# yard-ice-power.net
KiCad netlist of a schematic drawn in Altium Designer
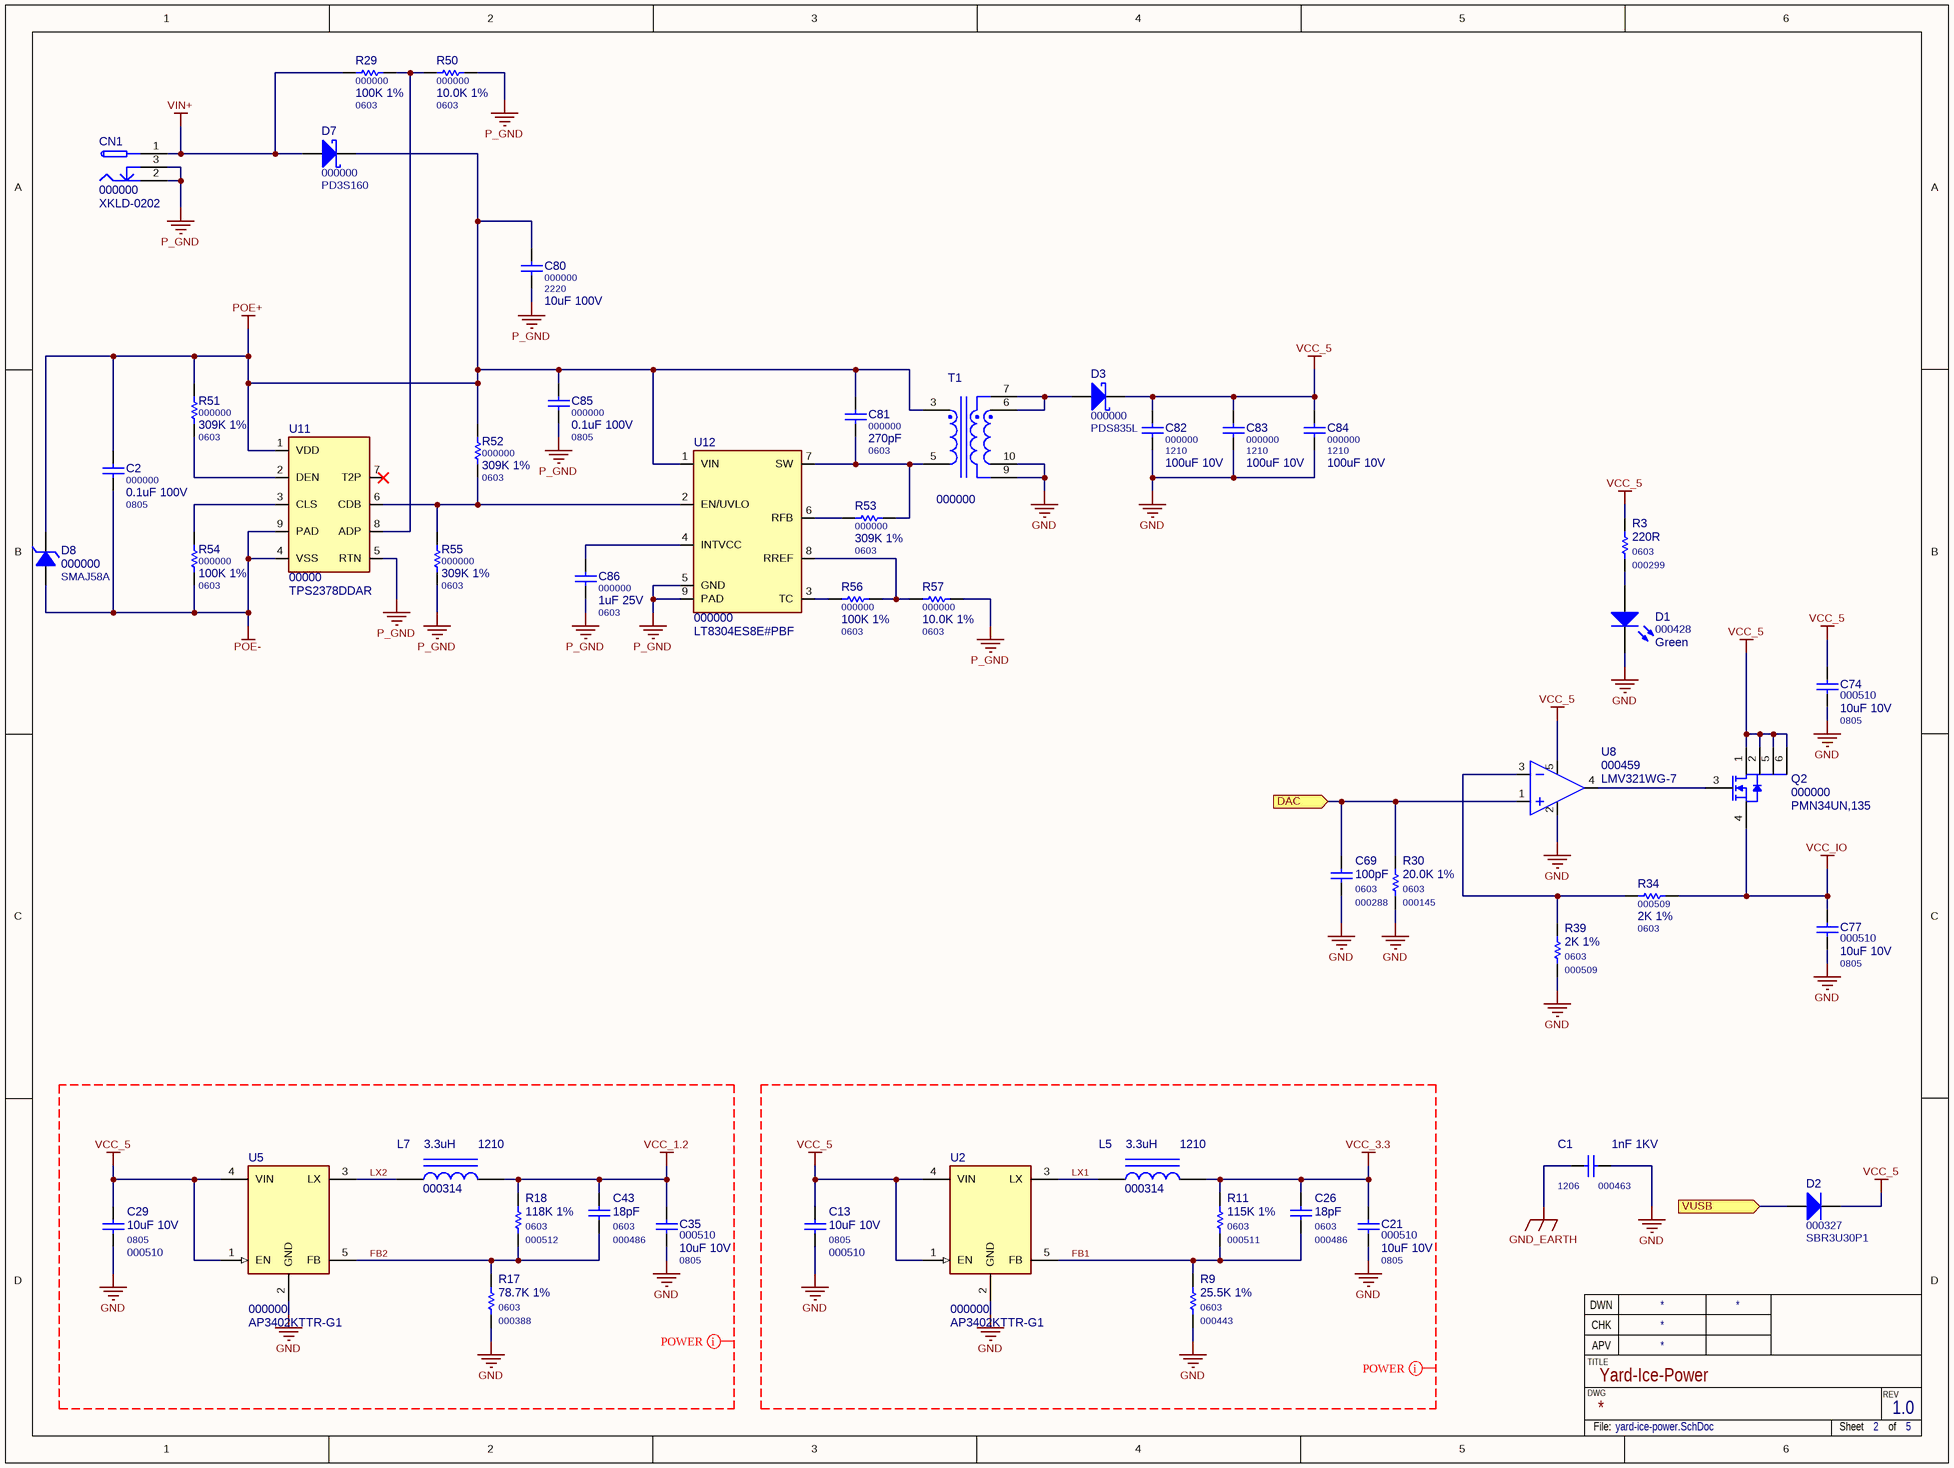
[diagram p0: yard-ice-power.SchDoc]

(export (version "E")
  (design (tool "Eeschema 10.0.6"))
  (components
    (comp (ref "C1")
      (value "000463")
      (footprint "C1206M")
      (description "SMD Ceramic Chip Capacitor - 1206")
      (fields (field (name "ALTIUM_VALUE") "1nF 1KV") (field (name "PACKAGE") "1206"))
      (libsource (lib "discrete-sm") (part "C1206"))
    )
    (comp (ref "C2")
      (value "000000")
      (footprint "C0805HV")
      (description "SMD Ceramic Chip Capacitor - 0805")
      (fields (field (name "ALTIUM_VALUE") "0.1uF 100V") (field (name "PACKAGE") "0805"))
      (libsource (lib "discrete-sm") (part "C0805"))
    )
    (comp (ref "C13")
      (value "000510")
      (footprint "C0805M")
      (description "SMD Ceramic Chip Capacitor - 0805 - X7R")
      (fields
        (field (name "ALTIUM_VALUE") "10uF 10V")
        (field (name "PACKAGE") "0805")
        (field (name "MF") "TDK")
      )
      (libsource (lib "sm_cap") (part "C0805"))
    )
    (comp (ref "C21")
      (value "000510")
      (footprint "C0805M")
      (description "SMD Ceramic Chip Capacitor - 0805 - X7R")
      (fields
        (field (name "ALTIUM_VALUE") "10uF 10V")
        (field (name "PACKAGE") "0805")
        (field (name "MF") "TDK")
      )
      (libsource (lib "sm_cap") (part "C0805"))
    )
    (comp (ref "C26")
      (value "000486")
      (footprint "C0603M")
      (description "SMD Ceramic Chip Capacitor - 0603")
      (fields (field (name "ALTIUM_VALUE") "18pF") (field (name "PACKAGE") "0603"))
      (libsource (lib "discrete-sm") (part "C0603"))
    )
    (comp (ref "C29")
      (value "000510")
      (footprint "C0805M")
      (description "SMD Ceramic Chip Capacitor - 0805 - X7R")
      (fields
        (field (name "ALTIUM_VALUE") "10uF 10V")
        (field (name "PACKAGE") "0805")
        (field (name "MF") "TDK")
      )
      (libsource (lib "sm_cap") (part "C0805"))
    )
    (comp (ref "C35")
      (value "000510")
      (footprint "C0805M")
      (description "SMD Ceramic Chip Capacitor - 0805 - X7R")
      (fields
        (field (name "ALTIUM_VALUE") "10uF 10V")
        (field (name "PACKAGE") "0805")
        (field (name "MF") "TDK")
      )
      (libsource (lib "sm_cap") (part "C0805"))
    )
    (comp (ref "C43")
      (value "000486")
      (footprint "C0603M")
      (description "SMD Ceramic Chip Capacitor - 0603")
      (fields (field (name "ALTIUM_VALUE") "18pF") (field (name "PACKAGE") "0603"))
      (libsource (lib "discrete-sm") (part "C0603"))
    )
    (comp (ref "C69")
      (value "000288")
      (footprint "C0603M")
      (description "SMD Ceramic Chip Capacitor - 0603")
      (fields (field (name "ALTIUM_VALUE") "100pF") (field (name "PACKAGE") "0603"))
      (libsource (lib "discrete-sm") (part "C0603"))
    )
    (comp (ref "C74")
      (value "TDK")
      (footprint "C0805M")
      (description "SMD Ceramic Chip Capacitor - 0805 - X7R")
      (fields (field (name "ALTIUM_VALUE") "10uF 10V") (field (name "PACKAGE") "0805"))
      (libsource (lib "sm_cap") (part "C0805"))
    )
    (comp (ref "C77")
      (value "TDK")
      (footprint "C0805M")
      (description "SMD Ceramic Chip Capacitor - 0805 - X7R")
      (fields (field (name "ALTIUM_VALUE") "10uF 10V") (field (name "PACKAGE") "0805"))
      (libsource (lib "sm_cap") (part "C0805"))
    )
    (comp (ref "C80")
      (value "000000")
      (footprint "C2220M")
      (description "SMD Ceramic Chip Capacitor - 2220")
      (fields
        (field (name "MF") "AVX")
        (field (name "PACKAGE") "2220")
        (field (name "ALTIUM_VALUE") "10uF 100V")
      )
      (libsource (lib "discrete-sm") (part "C2220"))
    )
    (comp (ref "C81")
      (value "000000")
      (footprint "C0603HV")
      (description "SMD Ceramic Chip Capacitor - 0603")
      (fields (field (name "ALTIUM_VALUE") "270pF") (field (name "PACKAGE") "0603"))
      (libsource (lib "discrete-sm") (part "C0603"))
    )
    (comp (ref "C82")
      (value "000000")
      (footprint "C1210M")
      (description "SMD Ceramic Chip Capacitor - 1210")
      (fields
        (field (name "PACKAGE") "1210")
        (field (name "ALTIUM_VALUE") "100uF 10V")
        (field (name "MF") "Taiyo Yuden")
      )
      (libsource (lib "discrete-sm") (part "C1210"))
    )
    (comp (ref "C83")
      (value "000000")
      (footprint "C1210M")
      (description "SMD Ceramic Chip Capacitor - 1210")
      (fields
        (field (name "PACKAGE") "1210")
        (field (name "ALTIUM_VALUE") "100uF 10V")
        (field (name "MF") "Taiyo Yuden")
      )
      (libsource (lib "discrete-sm") (part "C1210"))
    )
    (comp (ref "C84")
      (value "000000")
      (footprint "C1210M")
      (description "SMD Ceramic Chip Capacitor - 1210")
      (fields
        (field (name "PACKAGE") "1210")
        (field (name "ALTIUM_VALUE") "100uF 10V")
        (field (name "MF") "Taiyo Yuden")
      )
      (libsource (lib "discrete-sm") (part "C1210"))
    )
    (comp (ref "C85")
      (value "000000")
      (footprint "C0805HV")
      (description "SMD Ceramic Chip Capacitor - 0805")
      (fields (field (name "ALTIUM_VALUE") "0.1uF 100V") (field (name "PACKAGE") "0805"))
      (libsource (lib "discrete-sm") (part "C0805"))
    )
    (comp (ref "C86")
      (value "000000")
      (footprint "C0603M")
      (description "SMD Ceramic Chip Capacitor - 0603")
      (fields (field (name "ALTIUM_VALUE") "1uF 25V") (field (name "PACKAGE") "0603"))
      (libsource (lib "discrete-sm") (part "C0603"))
    )
    (comp (ref "CN1")
      (value "000000")
      (footprint "KLDX-0202")
      (description "Low Voltage Power Supply Connector")
      (fields (field (name "MF") "KYCON") (field (name "ALTIUM_VALUE") "XKLD-0202"))
      (libsource (lib "kycon") (part "XKLD-0202"))
    )
    (comp (ref "D1")
      (value "000428")
      (footprint "LED0805L LP")
      (description "LED SMD 0805")
      (fields (field (name "ALTIUM_VALUE") "Green"))
      (libsource (lib "discrete-sm") (part "LED0805LP"))
    )
    (comp (ref "D2")
      (value "000327")
      (footprint "PowerDI 123")
      (description "Super Barrier Rectifier")
      (fields (field (name "ALTIUM_VALUE") "SBR3U30P1") (field (name "MF") "Diodes Inc"))
      (libsource (lib "diodes-inc") (part "SBR3U30P1"))
    )
    (comp (ref "D3")
      (value "000000")
      (footprint "PowerDI 5")
      (description "Shottky Barrier Rectifier 25V 8A")
      (fields (field (name "ALTIUM_VALUE") "PDS835L") (field (name "MF") "Diodes Inc"))
      (libsource (lib "diodes-inc") (part "PDS835L"))
    )
    (comp (ref "D7")
      (value "000000")
      (footprint "PowerDI 123")
      (description "Sshottky Barrier Rectifier 60V 1A")
      (fields (field (name "ALTIUM_VALUE") "PD3S160") (field (name "MF") "Diodes Inc"))
      (libsource (lib "diodes-inc") (part "PD3S160"))
    )
    (comp (ref "D8")
      (value "000000")
      (footprint "DO-214AC")
      (description "Unidirectional Transiet Voltage Suppressor")
      (fields (field (name "ALTIUM_VALUE") "SMAJ58A") (field (name "MF") "Bourns"))
      (libsource (lib "bourns") (part "SMAJXXA"))
    )
    (comp (ref "L5")
      (value "000314")
      (footprint "L1210M")
      (description "SMD Wire Wound Inductor -  1210 (3225 metric)")
      (fields
        (field (name "MF") "Murata")
        (field (name "PACKAGE") "1210")
        (field (name "ALTIUM_VALUE") "3.3uH")
      )
      (libsource (lib "discrete-sm") (part "L1210"))
    )
    (comp (ref "L7")
      (value "000314")
      (footprint "L1210M")
      (description "SMD Wire Wound Inductor -  1210 (3225 metric)")
      (fields
        (field (name "MF") "Murata")
        (field (name "PACKAGE") "1210")
        (field (name "ALTIUM_VALUE") "3.3uH")
      )
      (libsource (lib "discrete-sm") (part "L1210"))
    )
    (comp (ref "Q2")
      (value "000000")
      (footprint "SOT-26")
      (description "N-Channel MOSFET 30V 4.9A 6TSOP")
      (fields (field (name "ALTIUM_VALUE") "PMN34UN,135"))
      (libsource (lib "nxp") (part "PMN34UN,135"))
    )
    (comp (ref "R3")
      (value "000299")
      (footprint "R0603M")
      (description "SMD Chip Resistor - 0603")
      (fields (field (name "ALTIUM_VALUE") "220R") (field (name "PACKAGE") "0603"))
      (libsource (lib "discrete-sm") (part "R0603"))
    )
    (comp (ref "R9")
      (value "000443")
      (footprint "R0603M")
      (description "SMD Chip Resistor - 0603")
      (fields (field (name "ALTIUM_VALUE") "25.5K 1%") (field (name "PACKAGE") "0603"))
      (libsource (lib "discrete-sm") (part "R0603"))
    )
    (comp (ref "R11")
      (value "000511")
      (footprint "R0603M")
      (description "SMD Chip Resistor - 0603")
      (fields (field (name "ALTIUM_VALUE") "115K 1%") (field (name "PACKAGE") "0603"))
      (libsource (lib "discrete-sm") (part "R0603"))
    )
    (comp (ref "R17")
      (value "000388")
      (footprint "R0603M")
      (description "SMD Chip Resistor - 0603")
      (fields (field (name "ALTIUM_VALUE") "78.7K 1%") (field (name "PACKAGE") "0603"))
      (libsource (lib "discrete-sm") (part "R0603"))
    )
    (comp (ref "R18")
      (value "000512")
      (footprint "R0603M")
      (description "SMD Chip Resistor - 0603")
      (fields (field (name "ALTIUM_VALUE") "118K 1%") (field (name "PACKAGE") "0603"))
      (libsource (lib "discrete-sm") (part "R0603"))
    )
    (comp (ref "R29")
      (value "000000")
      (footprint "R0603M")
      (description "SMD Chip Resistor - 0603")
      (fields (field (name "ALTIUM_VALUE") "100K 1%") (field (name "PACKAGE") "0603"))
      (libsource (lib "discrete-sm") (part "R0603"))
    )
    (comp (ref "R30")
      (value "000145")
      (footprint "R0603M")
      (description "SMD Chip Resistor - 0603")
      (fields (field (name "ALTIUM_VALUE") "20.0K 1%") (field (name "PACKAGE") "0603"))
      (libsource (lib "discrete-sm") (part "R0603"))
    )
    (comp (ref "R34")
      (value "000509")
      (footprint "R0603M")
      (description "SMD Chip Resistor - 0603")
      (fields (field (name "ALTIUM_VALUE") "2K 1%") (field (name "PACKAGE") "0603"))
      (libsource (lib "discrete-sm") (part "R0603"))
    )
    (comp (ref "R39")
      (value "000509")
      (footprint "R0603M")
      (description "SMD Chip Resistor - 0603")
      (fields (field (name "ALTIUM_VALUE") "2K 1%") (field (name "PACKAGE") "0603"))
      (libsource (lib "discrete-sm") (part "R0603"))
    )
    (comp (ref "R50")
      (value "000000")
      (footprint "R0603M")
      (description "SMD Chip Resistor - 0603")
      (fields (field (name "ALTIUM_VALUE") "10.0K 1%") (field (name "PACKAGE") "0603"))
      (libsource (lib "discrete-sm") (part "R0603"))
    )
    (comp (ref "R51")
      (value "000000")
      (footprint "R0603HV")
      (description "SMD Chip Resistor - 0603")
      (fields (field (name "ALTIUM_VALUE") "309K 1%") (field (name "PACKAGE") "0603"))
      (libsource (lib "discrete-sm") (part "R0603"))
    )
    (comp (ref "R52")
      (value "000000")
      (footprint "R0603HV")
      (description "SMD Chip Resistor - 0603")
      (fields (field (name "ALTIUM_VALUE") "309K 1%") (field (name "PACKAGE") "0603"))
      (libsource (lib "discrete-sm") (part "R0603"))
    )
    (comp (ref "R53")
      (value "000000")
      (footprint "R0603HV")
      (description "SMD Chip Resistor - 0603")
      (fields (field (name "ALTIUM_VALUE") "309K 1%") (field (name "PACKAGE") "0603"))
      (libsource (lib "discrete-sm") (part "R0603"))
    )
    (comp (ref "R54")
      (value "000000")
      (footprint "R0603M")
      (description "SMD Chip Resistor - 0603")
      (fields (field (name "ALTIUM_VALUE") "100K 1%") (field (name "PACKAGE") "0603"))
      (libsource (lib "discrete-sm") (part "R0603"))
    )
    (comp (ref "R55")
      (value "000000")
      (footprint "R0603HV")
      (description "SMD Chip Resistor - 0603")
      (fields (field (name "ALTIUM_VALUE") "309K 1%") (field (name "PACKAGE") "0603"))
      (libsource (lib "discrete-sm") (part "R0603"))
    )
    (comp (ref "R56")
      (value "000000")
      (footprint "R0603M")
      (description "SMD Chip Resistor - 0603")
      (fields (field (name "ALTIUM_VALUE") "100K 1%") (field (name "PACKAGE") "0603"))
      (libsource (lib "discrete-sm") (part "R0603"))
    )
    (comp (ref "R57")
      (value "000000")
      (footprint "R0603M")
      (description "SMD Chip Resistor - 0603")
      (fields (field (name "ALTIUM_VALUE") "10.0K 1%") (field (name "PACKAGE") "0603"))
      (libsource (lib "discrete-sm") (part "R0603"))
    )
    (comp (ref "T1")
      (value "000000")
      (footprint "75031583X")
      (description "SMD Transformer")
      (fields (field (name "MF") "Wurth"))
      (libsource (lib "wurth") (part "750315126"))
    )
    (comp (ref "U2")
      (value "000000")
      (footprint "SOT23-5-M")
      (description "2A Step-Down DC/DC Cnverter 1MHz Switching Frequency")
      (fields (field (name "MF") "Diodes Inc") (field (name "ALTIUM_VALUE") "AP3402KTTR-G1"))
      (libsource (lib "diodes-inc") (part "AP3429A"))
    )
    (comp (ref "U5")
      (value "000000")
      (footprint "SOT23-5-M")
      (description "2A Step-Down DC/DC Cnverter 1MHz Switching Frequency")
      (fields (field (name "MF") "Diodes Inc") (field (name "ALTIUM_VALUE") "AP3402KTTR-G1"))
      (libsource (lib "diodes-inc") (part "AP3429A"))
    )
    (comp (ref "U8")
      (value "000459")
      (footprint "SOT-25")
      (description "General Purpose, Low Voltage, Rail-to-Rail Output Operational Amplifier")
      (fields (field (name "ALTIUM_VALUE") "LMV321WG-7") (field (name "MF") "Diodes Inc"))
      (libsource (lib "diodes-inc-opamp") (part "LMV321WG-7"))
    )
    (comp (ref "U11")
      (value "00000")
      (footprint "DDA (R-PDSO-G8)")
      (description "PoE High-Power PD Interface")
      (fields (field (name "MF") "Texas Instruments") (field (name "ALTIUM_VALUE") "TPS2378DDAR"))
      (libsource (lib "texas-instruments") (part "TPS2378"))
    )
    (comp (ref "U12")
      (value "000000")
      (footprint "S8E")
      (description "100V Isolated Flyback Converter")
      (fields (field (name "MF") "Linear Technology") (field (name "ALTIUM_VALUE") "LT8304ES8E#PBF"))
      (libsource (lib "lt-power") (part "LT3804"))
    )
  )
  (nets
    (net (code "1") (name "/DAC") (class "Default")
      (node (ref "C69") (pin "1") (pinfunction "1_1") (pintype "passive"))
      (node (ref "R30") (pin "2") (pinfunction "2_2") (pintype "passive"))
      (node (ref "U8") (pin "1") (pinfunction "IN+_1") (pintype "passive"))
    )
    (net (code "2") (name "/FB1") (class "Default")
      (node (ref "C26") (pin "2") (pinfunction "2_2") (pintype "passive"))
      (node (ref "R11") (pin "1") (pinfunction "1_1") (pintype "passive"))
      (node (ref "R9") (pin "2") (pinfunction "2_2") (pintype "passive"))
      (node (ref "U2") (pin "5") (pinfunction "FB_5") (pintype "passive"))
    )
    (net (code "3") (name "/FB2") (class "Default")
      (node (ref "C43") (pin "2") (pinfunction "2_2") (pintype "passive"))
      (node (ref "R17") (pin "2") (pinfunction "2_2") (pintype "passive"))
      (node (ref "R18") (pin "1") (pinfunction "1_1") (pintype "passive"))
      (node (ref "U5") (pin "5") (pinfunction "FB_5") (pintype "passive"))
    )
    (net (code "4") (name "/LX1") (class "Default")
      (node (ref "L5") (pin "1") (pinfunction "1_1") (pintype "passive"))
      (node (ref "U2") (pin "3") (pinfunction "LX_3") (pintype "open_collector"))
    )
    (net (code "5") (name "/LX2") (class "Default")
      (node (ref "L7") (pin "1") (pinfunction "1_1") (pintype "passive"))
      (node (ref "U5") (pin "3") (pinfunction "LX_3") (pintype "open_collector"))
    )
    (net (code "6") (name "/VUSB") (class "Default")
      (node (ref "D2") (pin "1") (pinfunction "A_1") (pintype "passive"))
    )
    (net (code "7") (name "GND") (class "Default")
      (node (ref "C1") (pin "2") (pinfunction "2_2") (pintype "passive"))
      (node (ref "C13") (pin "2") (pinfunction "2_2") (pintype "passive"))
      (node (ref "C21") (pin "2") (pinfunction "2_2") (pintype "passive"))
      (node (ref "C29") (pin "2") (pinfunction "2_2") (pintype "passive"))
      (node (ref "C35") (pin "2") (pinfunction "2_2") (pintype "passive"))
      (node (ref "C69") (pin "2") (pinfunction "2_2") (pintype "passive"))
      (node (ref "C74") (pin "2") (pinfunction "2_2") (pintype "passive"))
      (node (ref "C77") (pin "2") (pinfunction "2_2") (pintype "passive"))
      (node (ref "C82") (pin "2") (pinfunction "2_2") (pintype "passive"))
      (node (ref "C83") (pin "2") (pinfunction "2_2") (pintype "passive"))
      (node (ref "C84") (pin "2") (pinfunction "2_2") (pintype "passive"))
      (node (ref "D1") (pin "2") (pinfunction "K_2") (pintype "passive"))
      (node (ref "R17") (pin "1") (pinfunction "1_1") (pintype "passive"))
      (node (ref "R30") (pin "1") (pinfunction "1_1") (pintype "passive"))
      (node (ref "R39") (pin "1") (pinfunction "1_1") (pintype "passive"))
      (node (ref "R9") (pin "1") (pinfunction "1_1") (pintype "passive"))
      (node (ref "T1") (pin "10") (pinfunction "10_10") (pintype "passive"))
      (node (ref "T1") (pin "9") (pinfunction "9_9") (pintype "passive"))
      (node (ref "U2") (pin "2") (pinfunction "GND_2") (pintype "power_in"))
      (node (ref "U5") (pin "2") (pinfunction "GND_2") (pintype "power_in"))
      (node (ref "U8") (pin "2") (pinfunction "V-_2") (pintype "power_in"))
    )
    (net (code "8") (name "GND_EARTH") (class "Default")
      (node (ref "C1") (pin "1") (pinfunction "1_1") (pintype "passive"))
    )
    (net (code "9") (name "Net-(D1-A)") (class "Default")
      (node (ref "D1") (pin "1") (pinfunction "A_1") (pintype "passive"))
      (node (ref "R3") (pin "1") (pinfunction "1_1") (pintype "passive"))
    )
    (net (code "10") (name "Net-(D3-A)") (class "Default")
      (node (ref "D3") (pin "1") (pinfunction "A_1") (pintype "passive"))
      (node (ref "T1") (pin "6") (pinfunction "6_6") (pintype "passive"))
      (node (ref "T1") (pin "7") (pinfunction "7_7") (pintype "passive"))
    )
    (net (code "11") (name "Net-(Q2-G)") (class "Default")
      (node (ref "Q2") (pin "3") (pinfunction "G_3") (pintype "passive"))
      (node (ref "U8") (pin "4") (pinfunction "OUT_4") (pintype "passive"))
    )
    (net (code "12") (name "Net-(U8-IN-)") (class "Default")
      (node (ref "R34") (pin "2") (pinfunction "2_2") (pintype "passive"))
      (node (ref "R39") (pin "2") (pinfunction "2_2") (pintype "passive"))
      (node (ref "U8") (pin "3") (pinfunction "IN-_3") (pintype "passive"))
    )
    (net (code "13") (name "Net-(U11-ADP)") (class "Default")
      (node (ref "R29") (pin "1") (pinfunction "1_1") (pintype "passive"))
      (node (ref "R50") (pin "2") (pinfunction "2_2") (pintype "passive"))
      (node (ref "U11") (pin "8") (pinfunction "ADP_8") (pintype "open_collector"))
    )
    (net (code "14") (name "Net-(U11-CDB)") (class "Default")
      (node (ref "R52") (pin "2") (pinfunction "2_2") (pintype "passive"))
      (node (ref "R55") (pin "1") (pinfunction "1_1") (pintype "passive"))
      (node (ref "U11") (pin "6") (pinfunction "CDB_6") (pintype "open_collector"))
      (node (ref "U12") (pin "2") (pinfunction "EN/UVLO_2") (pintype "open_collector"))
    )
    (net (code "15") (name "Net-(U11-CLS)") (class "Default")
      (node (ref "R54") (pin "1") (pinfunction "1_1") (pintype "passive"))
      (node (ref "U11") (pin "3") (pinfunction "CLS_3") (pintype "passive"))
    )
    (net (code "16") (name "Net-(U11-DEN)") (class "Default")
      (node (ref "R51") (pin "2") (pinfunction "2_2") (pintype "passive"))
      (node (ref "U11") (pin "2") (pinfunction "DEN_2") (pintype "open_collector"))
    )
    (net (code "17") (name "Net-(U12-INTVCC)") (class "Default")
      (node (ref "C86") (pin "1") (pinfunction "1_1") (pintype "passive"))
      (node (ref "U12") (pin "4") (pinfunction "INTVCC_4") (pintype "power_in"))
    )
    (net (code "18") (name "Net-(U12-RFB)") (class "Default")
      (node (ref "R53") (pin "2") (pinfunction "2_2") (pintype "passive"))
      (node (ref "U12") (pin "6") (pinfunction "RFB_6") (pintype "open_collector"))
    )
    (net (code "19") (name "Net-(U12-RREF)") (class "Default")
      (node (ref "R56") (pin "1") (pinfunction "1_1") (pintype "passive"))
      (node (ref "R57") (pin "2") (pinfunction "2_2") (pintype "passive"))
      (node (ref "U12") (pin "8") (pinfunction "RREF_8") (pintype "open_collector"))
    )
    (net (code "20") (name "Net-(U12-SW)") (class "Default")
      (node (ref "C81") (pin "2") (pinfunction "2_2") (pintype "passive"))
      (node (ref "R53") (pin "1") (pinfunction "1_1") (pintype "passive"))
      (node (ref "T1") (pin "5") (pinfunction "5_5") (pintype "passive"))
      (node (ref "U12") (pin "7") (pinfunction "SW_7") (pintype "passive"))
    )
    (net (code "21") (name "Net-(U12-TC)") (class "Default")
      (node (ref "R56") (pin "2") (pinfunction "2_2") (pintype "passive"))
      (node (ref "U12") (pin "3") (pinfunction "TC_3") (pintype "passive"))
    )
    (net (code "22") (name "POE+") (class "Default")
      (node (ref "C2") (pin "1") (pinfunction "1_1") (pintype "passive"))
      (node (ref "C80") (pin "1") (pinfunction "1_1") (pintype "passive"))
      (node (ref "C81") (pin "1") (pinfunction "1_1") (pintype "passive"))
      (node (ref "C85") (pin "1") (pinfunction "1_1") (pintype "passive"))
      (node (ref "D7") (pin "2") (pinfunction "K_2") (pintype "passive"))
      (node (ref "D8") (pin "2") (pinfunction "K_2") (pintype "passive"))
      (node (ref "R51") (pin "1") (pinfunction "1_1") (pintype "passive"))
      (node (ref "R52") (pin "1") (pinfunction "1_1") (pintype "passive"))
      (node (ref "T1") (pin "3") (pinfunction "3_3") (pintype "passive"))
      (node (ref "U11") (pin "1") (pinfunction "VDD_1") (pintype "power_in"))
      (node (ref "U12") (pin "1") (pinfunction "VIN_1") (pintype "power_in"))
    )
    (net (code "23") (name "POE-") (class "Default")
      (node (ref "C2") (pin "2") (pinfunction "2_2") (pintype "passive"))
      (node (ref "D8") (pin "1") (pinfunction "A_1") (pintype "passive"))
      (node (ref "R54") (pin "2") (pinfunction "2_2") (pintype "passive"))
      (node (ref "U11") (pin "4") (pinfunction "VSS_4") (pintype "power_in"))
      (node (ref "U11") (pin "9") (pinfunction "PAD_9") (pintype "power_in"))
    )
    (net (code "24") (name "P_GND") (class "Default")
      (node (ref "C80") (pin "2") (pinfunction "2_2") (pintype "passive"))
      (node (ref "C85") (pin "2") (pinfunction "2_2") (pintype "passive"))
      (node (ref "C86") (pin "2") (pinfunction "2_2") (pintype "passive"))
      (node (ref "CN1") (pin "2") (pinfunction "2_2") (pintype "power_in"))
      (node (ref "CN1") (pin "3") (pinfunction "3_3") (pintype "power_in"))
      (node (ref "R50") (pin "1") (pinfunction "1_1") (pintype "passive"))
      (node (ref "R55") (pin "2") (pinfunction "2_2") (pintype "passive"))
      (node (ref "R57") (pin "1") (pinfunction "1_1") (pintype "passive"))
      (node (ref "U11") (pin "5") (pinfunction "RTN_5") (pintype "passive"))
      (node (ref "U12") (pin "5") (pinfunction "GND_5") (pintype "passive"))
      (node (ref "U12") (pin "9") (pinfunction "PAD_9") (pintype "power_in"))
    )
    (net (code "25") (name "VCC_1.2") (class "Default")
      (node (ref "C35") (pin "1") (pinfunction "1_1") (pintype "passive"))
      (node (ref "C43") (pin "1") (pinfunction "1_1") (pintype "passive"))
      (node (ref "L7") (pin "2") (pinfunction "2_2") (pintype "passive"))
      (node (ref "R18") (pin "2") (pinfunction "2_2") (pintype "passive"))
    )
    (net (code "26") (name "VCC_3.3") (class "Default")
      (node (ref "C21") (pin "1") (pinfunction "1_1") (pintype "passive"))
      (node (ref "C26") (pin "1") (pinfunction "1_1") (pintype "passive"))
      (node (ref "L5") (pin "2") (pinfunction "2_2") (pintype "passive"))
      (node (ref "R11") (pin "2") (pinfunction "2_2") (pintype "passive"))
    )
    (net (code "27") (name "VCC_5") (class "Default")
      (node (ref "C13") (pin "1") (pinfunction "1_1") (pintype "passive"))
      (node (ref "C29") (pin "1") (pinfunction "1_1") (pintype "passive"))
      (node (ref "C74") (pin "1") (pinfunction "1_1") (pintype "passive"))
      (node (ref "C82") (pin "1") (pinfunction "1_1") (pintype "passive"))
      (node (ref "C83") (pin "1") (pinfunction "1_1") (pintype "passive"))
      (node (ref "C84") (pin "1") (pinfunction "1_1") (pintype "passive"))
      (node (ref "D2") (pin "2") (pinfunction "K_2") (pintype "passive"))
      (node (ref "D3") (pin "2") (pinfunction "K_2") (pintype "passive"))
      (node (ref "Q2") (pin "1") (pinfunction "D_1") (pintype "passive"))
      (node (ref "Q2") (pin "2") (pinfunction "D_2") (pintype "passive"))
      (node (ref "Q2") (pin "5") (pinfunction "D_5") (pintype "passive"))
      (node (ref "Q2") (pin "6") (pinfunction "D_6") (pintype "passive"))
      (node (ref "R3") (pin "2") (pinfunction "2_2") (pintype "passive"))
      (node (ref "U2") (pin "1") (pinfunction "EN_1") (pintype "input"))
      (node (ref "U2") (pin "4") (pinfunction "VIN_4") (pintype "power_in"))
      (node (ref "U5") (pin "1") (pinfunction "EN_1") (pintype "input"))
      (node (ref "U5") (pin "4") (pinfunction "VIN_4") (pintype "power_in"))
      (node (ref "U8") (pin "5") (pinfunction "V+_5") (pintype "power_in"))
    )
    (net (code "28") (name "VCC_IO") (class "Default")
      (node (ref "C77") (pin "1") (pinfunction "1_1") (pintype "passive"))
      (node (ref "Q2") (pin "4") (pinfunction "S_4") (pintype "passive"))
      (node (ref "R34") (pin "1") (pinfunction "1_1") (pintype "passive"))
    )
    (net (code "29") (name "VIN+") (class "Default")
      (node (ref "CN1") (pin "1") (pinfunction "1_1") (pintype "power_in"))
      (node (ref "D7") (pin "1") (pinfunction "A_1") (pintype "passive"))
      (node (ref "R29") (pin "2") (pinfunction "2_2") (pintype "passive"))
    )
    (net (code "30") (name "unconnected-(U11-T2P-Pad7)") (class "Default")
      (node (ref "U11") (pin "7") (pinfunction "T2P_7") (pintype "passive+no_connect"))
    )
  )
)
